# Launch_Tower_Ignition_Board_v6-3.net
KiCad netlist of a schematic drawn in EAGLE
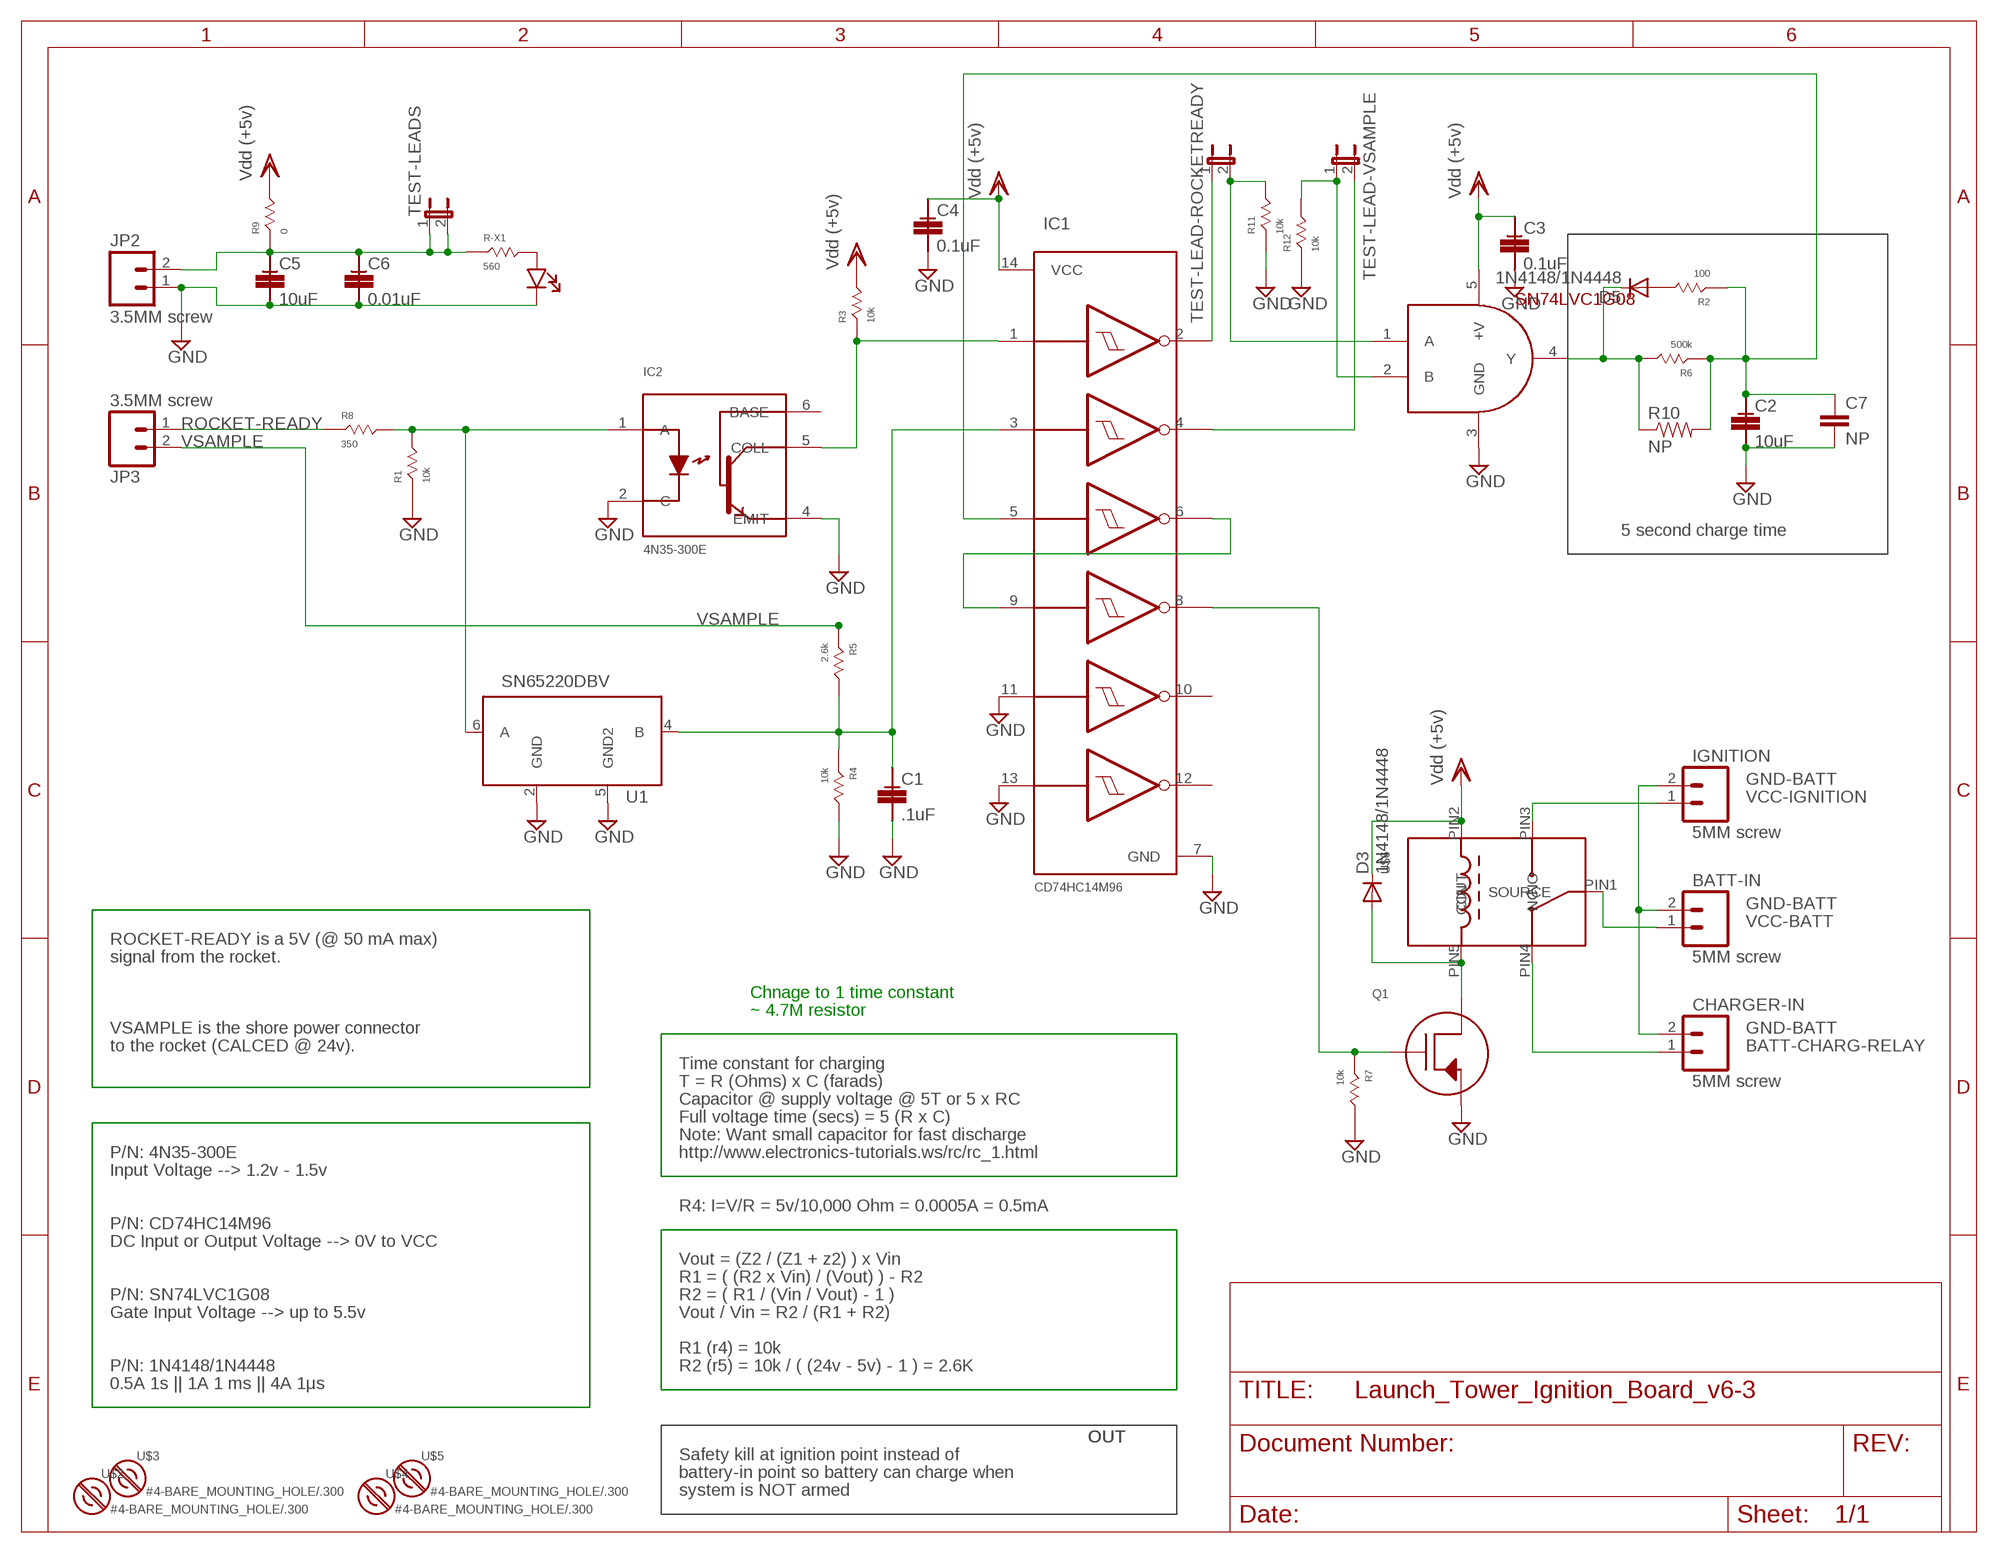
[diagram p0: schematic, sheet 1]

(export (version "E")
  (design (tool "Eeschema 10.0.6"))
  (components
    (comp (ref "BATT-IN")
      (value "5MM screw")
      (footprint "eagle-import:SCREWTERMINAL-5MM-2")
      (libsource (lib "eagle-import") (part "M025MM"))
    )
    (comp (ref "C1")
      (value ".1uF")
      (footprint "eagle-import:0805")
      (libsource (lib "eagle-import") (part "CAPACITOR-0805"))
    )
    (comp (ref "C2")
      (value "10uF")
      (footprint "eagle-import:0805")
      (libsource (lib "eagle-import") (part "CAPACITOR-0805"))
    )
    (comp (ref "C3")
      (value "0.1uF")
      (footprint "eagle-import:0805")
      (libsource (lib "eagle-import") (part "CAPACITOR-0805"))
    )
    (comp (ref "C4")
      (value "0.1uF")
      (footprint "eagle-import:0805")
      (libsource (lib "eagle-import") (part "CAPACITOR-0805"))
    )
    (comp (ref "C5")
      (value "10uF")
      (footprint "eagle-import:0805")
      (libsource (lib "eagle-import") (part "CAPACITOR-0805"))
    )
    (comp (ref "C6")
      (value "0.01uF")
      (footprint "eagle-import:0805")
      (libsource (lib "eagle-import") (part "CAPACITOR-0805"))
    )
    (comp (ref "C7")
      (value "NP")
      (footprint "eagle-import:CAP-PTH-SMALL")
      (libsource (lib "eagle-import") (part "CAPPTH"))
    )
    (comp (ref "CHARGER-IN")
      (value "5MM screw")
      (footprint "eagle-import:SCREWTERMINAL-5MM-2")
      (libsource (lib "eagle-import") (part "M025MM"))
    )
    (comp (ref "D3")
      (value "1N4148/1N4448")
      (footprint "eagle-import:DIODE-1N4001")
      (libsource (lib "eagle-import") (part "DIODEPTH"))
    )
    (comp (ref "D5")
      (value "1N4148/1N4448")
      (footprint "eagle-import:DIODE-1N4001")
      (libsource (lib "eagle-import") (part "DIODEPTH"))
    )
    (comp (ref "IC1")
      (value "INVERT GATES")
      (footprint "eagle-import:INVERTSOIC14")
      (libsource (lib "eagle-import") (part "HEX_INV_SHMITT_TRIG"))
    )
    (comp (ref "IC2")
      (value "OPTOISOLATOR")
      (footprint "eagle-import:4N35-300E")
      (libsource (lib "eagle-import") (part "OPTOISOLATOR"))
    )
    (comp (ref "IGNITION")
      (value "5MM screw")
      (footprint "eagle-import:SCREWTERMINAL-5MM-2")
      (libsource (lib "eagle-import") (part "M025MM"))
    )
    (comp (ref "JP2")
      (value "3.5MM screw")
      (footprint "eagle-import:SCREWTERMINAL-3.5MM-2")
      (libsource (lib "eagle-import") (part "M023.5MM"))
    )
    (comp (ref "JP3")
      (value "3.5MM screw")
      (footprint "eagle-import:SCREWTERMINAL-3.5MM-2")
      (libsource (lib "eagle-import") (part "M023.5MM"))
    )
    (comp (ref "LED-POWER-INDICATOR")
      (value "LED-550-XX04")
      (footprint "eagle-import:LED-550")
      (libsource (lib "eagle-import") (part "LED-550-XX04"))
    )
    (comp (ref "Q1")
      (value "NMOSFET")
      (footprint "eagle-import:FETSO-8")
      (libsource (lib "eagle-import") (part "NMOSFET"))
    )
    (comp (ref "R-X1")
      (value "560")
      (footprint "eagle-import:0805")
      (libsource (lib "eagle-import") (part "RESISTOR-0805"))
    )
    (comp (ref "R1")
      (value "10k")
      (footprint "eagle-import:0805")
      (libsource (lib "eagle-import") (part "RESISTOR-0805"))
    )
    (comp (ref "R2")
      (value "100")
      (footprint "eagle-import:0805")
      (libsource (lib "eagle-import") (part "RESISTOR-0805"))
    )
    (comp (ref "R3")
      (value "10k")
      (footprint "eagle-import:0805")
      (libsource (lib "eagle-import") (part "RESISTOR-0805"))
    )
    (comp (ref "R4")
      (value "10k")
      (footprint "eagle-import:0805")
      (libsource (lib "eagle-import") (part "RESISTOR-0805"))
    )
    (comp (ref "R5")
      (value "2.6k")
      (footprint "eagle-import:0805")
      (libsource (lib "eagle-import") (part "RESISTOR-0805"))
    )
    (comp (ref "R6")
      (value "500k")
      (footprint "eagle-import:0805")
      (libsource (lib "eagle-import") (part "RESISTOR-0805"))
    )
    (comp (ref "R7")
      (value "10k")
      (footprint "eagle-import:0805")
      (libsource (lib "eagle-import") (part "RESISTOR-0805"))
    )
    (comp (ref "R8")
      (value "350")
      (footprint "eagle-import:0805")
      (libsource (lib "eagle-import") (part "RESISTOR-0805"))
    )
    (comp (ref "R9")
      (value "0")
      (footprint "eagle-import:0805")
      (libsource (lib "eagle-import") (part "RESISTOR-0805"))
    )
    (comp (ref "R10")
      (value "NP")
      (footprint "eagle-import:AXIAL-0.4")
      (libsource (lib "eagle-import") (part "RESISTORPTH-1/4W"))
    )
    (comp (ref "R11")
      (value "10k")
      (footprint "eagle-import:0805")
      (libsource (lib "eagle-import") (part "RESISTOR-0805"))
    )
    (comp (ref "R12")
      (value "10k")
      (footprint "eagle-import:0805")
      (libsource (lib "eagle-import") (part "RESISTOR-0805"))
    )
    (comp (ref "TEST-LEAD-ROCKETREADY")
      (value "JUMPER-2PTH")
      (footprint "eagle-import:1X02")
      (libsource (lib "eagle-import") (part "JUMPER-2PTH"))
    )
    (comp (ref "TEST-LEAD-VSAMPLE")
      (value "JUMPER-2PTH")
      (footprint "eagle-import:1X02")
      (libsource (lib "eagle-import") (part "JUMPER-2PTH"))
    )
    (comp (ref "TEST-LEADS")
      (value "JUMPER-2PTH")
      (footprint "eagle-import:1X02")
      (libsource (lib "eagle-import") (part "JUMPER-2PTH"))
    )
    (comp (ref "U$1")
      (value "AND GATE")
      (footprint "eagle-import:SOT23-5")
      (libsource (lib "eagle-import") (part "SN74LVC1G08"))
    )
    (comp (ref "U$2")
      (value "#4-BARE_MOUNTING_HOLE/.300")
      (footprint "eagle-import:#4_.300-BARE+STD_NUT_OR_STAR_WASHER")
      (libsource (lib "eagle-import") (part "#4-BARE_MOUNTING_HOLE/.300"))
    )
    (comp (ref "U$3")
      (value "#4-BARE_MOUNTING_HOLE/.300")
      (footprint "eagle-import:#4_.300-BARE+STD_NUT_OR_STAR_WASHER")
      (libsource (lib "eagle-import") (part "#4-BARE_MOUNTING_HOLE/.300"))
    )
    (comp (ref "U$4")
      (value "#4-BARE_MOUNTING_HOLE/.300")
      (footprint "eagle-import:#4_.300-BARE+STD_NUT_OR_STAR_WASHER")
      (libsource (lib "eagle-import") (part "#4-BARE_MOUNTING_HOLE/.300"))
    )
    (comp (ref "U$5")
      (value "#4-BARE_MOUNTING_HOLE/.300")
      (footprint "eagle-import:#4_.300-BARE+STD_NUT_OR_STAR_WASHER")
      (libsource (lib "eagle-import") (part "#4-BARE_MOUNTING_HOLE/.300"))
    )
    (comp (ref "U$6")
      (value "RELAY-2")
      (footprint "eagle-import:G5LA")
      (libsource (lib "eagle-import") (part "RELAY-2"))
    )
    (comp (ref "U1")
      (value "SN65220DBV")
      (footprint "eagle-import:SOT23-6L")
      (libsource (lib "eagle-import") (part "SN65220DBV"))
    )
  )
  (nets
    (net (code "1") (name "/BATT-CHARG-RELAY") (class "Default")
      (node (ref "CHARGER-IN") (pin "1") (pinfunction "1_1") (pintype "passive"))
      (node (ref "U$6") (pin "PIN4") (pinfunction "NC_PIN4") (pintype "bidirectional"))
    )
    (net (code "2") (name "/GND-BATT") (class "Default")
      (node (ref "BATT-IN") (pin "2") (pinfunction "2_2") (pintype "passive"))
      (node (ref "CHARGER-IN") (pin "2") (pinfunction "2_2") (pintype "passive"))
      (node (ref "IGNITION") (pin "2") (pinfunction "2_2") (pintype "passive"))
    )
    (net (code "3") (name "/ROCKET-READY") (class "Default")
      (node (ref "IC2") (pin "1") (pinfunction "A_1") (pintype "bidirectional"))
      (node (ref "R1") (pin "CATHODE") (pinfunction "CATHODE_CATHODE") (pintype "bidirectional"))
      (node (ref "R8") (pin "CATHODE") (pinfunction "CATHODE_CATHODE") (pintype "bidirectional"))
      (node (ref "U1") (pin "6") (pinfunction "A_6") (pintype "passive"))
    )
    (net (code "4") (name "/VCC-BATT") (class "Default")
      (node (ref "BATT-IN") (pin "1") (pinfunction "1_1") (pintype "passive"))
      (node (ref "U$6") (pin "PIN1") (pinfunction "SOURCE_PIN1") (pintype "bidirectional"))
    )
    (net (code "5") (name "/VCC-IGNITION") (class "Default")
      (node (ref "IGNITION") (pin "1") (pinfunction "1_1") (pintype "passive"))
      (node (ref "U$6") (pin "PIN3") (pinfunction "NO_PIN3") (pintype "bidirectional"))
    )
    (net (code "6") (name "/VSAMPLE") (class "Default")
      (node (ref "JP3") (pin "2") (pinfunction "2_2") (pintype "passive"))
      (node (ref "R5") (pin "ANODE") (pinfunction "ANODE_ANODE") (pintype "bidirectional"))
    )
    (net (code "7") (name "GND") (class "Default")
      (node (ref "C1") (pin "CATHODE") (pinfunction "CATHODE_CATHODE") (pintype "bidirectional"))
      (node (ref "C2") (pin "CATHODE") (pinfunction "CATHODE_CATHODE") (pintype "bidirectional"))
      (node (ref "C3") (pin "CATHODE") (pinfunction "CATHODE_CATHODE") (pintype "bidirectional"))
      (node (ref "C4") (pin "CATHODE") (pinfunction "CATHODE_CATHODE") (pintype "bidirectional"))
      (node (ref "C5") (pin "CATHODE") (pinfunction "CATHODE_CATHODE") (pintype "bidirectional"))
      (node (ref "C6") (pin "CATHODE") (pinfunction "CATHODE_CATHODE") (pintype "bidirectional"))
      (node (ref "C7") (pin "2") (pinfunction "2_2") (pintype "passive"))
      (node (ref "IC1") (pin "11") (pinfunction "5A_11") (pintype "input"))
      (node (ref "IC1") (pin "13") (pinfunction "6A_13") (pintype "input"))
      (node (ref "IC1") (pin "7") (pinfunction "GND_7") (pintype "bidirectional"))
      (node (ref "IC2") (pin "2") (pinfunction "C_2") (pintype "bidirectional"))
      (node (ref "IC2") (pin "4") (pinfunction "EMIT_4") (pintype "bidirectional"))
      (node (ref "JP2") (pin "1") (pinfunction "1_1") (pintype "passive"))
      (node (ref "LED-POWER-INDICATOR") (pin "CATHODE") (pinfunction "CATHODE_CATHODE") (pintype "bidirectional"))
      (node (ref "Q1") (pin "1") (pinfunction "SOURCE_1") (pintype "bidirectional"))
      (node (ref "R1") (pin "ANODE") (pinfunction "ANODE_ANODE") (pintype "bidirectional"))
      (node (ref "R11") (pin "ANODE") (pinfunction "ANODE_ANODE") (pintype "bidirectional"))
      (node (ref "R12") (pin "ANODE") (pinfunction "ANODE_ANODE") (pintype "bidirectional"))
      (node (ref "R4") (pin "CATHODE") (pinfunction "CATHODE_CATHODE") (pintype "bidirectional"))
      (node (ref "R7") (pin "CATHODE") (pinfunction "CATHODE_CATHODE") (pintype "bidirectional"))
      (node (ref "U$1") (pin "3") (pinfunction "GND_3") (pintype "bidirectional"))
      (node (ref "U1") (pin "2") (pinfunction "GND_2") (pintype "power_in"))
      (node (ref "U1") (pin "5") (pinfunction "GND2_5") (pintype "power_in"))
    )
    (net (code "8") (name "Net-(C5-PadANODE)") (class "Default")
      (node (ref "C5") (pin "ANODE") (pinfunction "ANODE_ANODE") (pintype "bidirectional"))
      (node (ref "C6") (pin "ANODE") (pinfunction "ANODE_ANODE") (pintype "bidirectional"))
      (node (ref "JP2") (pin "2") (pinfunction "2_2") (pintype "passive"))
      (node (ref "R-X1") (pin "ANODE") (pinfunction "ANODE_ANODE") (pintype "bidirectional"))
      (node (ref "R9") (pin "ANODE") (pinfunction "ANODE_ANODE") (pintype "bidirectional"))
      (node (ref "TEST-LEADS") (pin "1") (pinfunction "1_1") (pintype "passive"))
      (node (ref "TEST-LEADS") (pin "2") (pinfunction "2_2") (pintype "passive"))
    )
    (net (code "9") (name "Net-(D5-PadA)") (class "Default")
      (node (ref "D5") (pin "A") (pinfunction "A_A") (pintype "passive"))
      (node (ref "R2") (pin "CATHODE") (pinfunction "CATHODE_CATHODE") (pintype "bidirectional"))
    )
    (net (code "10") (name "Net-(IC1-1A)") (class "Default")
      (node (ref "IC1") (pin "1") (pinfunction "1A_1") (pintype "input"))
      (node (ref "IC2") (pin "5") (pinfunction "COLL_5") (pintype "bidirectional"))
      (node (ref "R3") (pin "ANODE") (pinfunction "ANODE_ANODE") (pintype "bidirectional"))
    )
    (net (code "11") (name "Net-(IC1-1Y)") (class "Default")
      (node (ref "IC1") (pin "2") (pinfunction "1Y_2") (pintype "output"))
      (node (ref "TEST-LEAD-ROCKETREADY") (pin "1") (pinfunction "1_1") (pintype "passive"))
    )
    (net (code "12") (name "Net-(IC1-2A)") (class "Default")
      (node (ref "C1") (pin "ANODE") (pinfunction "ANODE_ANODE") (pintype "bidirectional"))
      (node (ref "IC1") (pin "3") (pinfunction "2A_3") (pintype "input"))
      (node (ref "R4") (pin "ANODE") (pinfunction "ANODE_ANODE") (pintype "bidirectional"))
      (node (ref "R5") (pin "CATHODE") (pinfunction "CATHODE_CATHODE") (pintype "bidirectional"))
      (node (ref "U1") (pin "4") (pinfunction "B_4") (pintype "passive"))
    )
    (net (code "13") (name "Net-(IC1-2Y)") (class "Default")
      (node (ref "IC1") (pin "4") (pinfunction "2Y_4") (pintype "output"))
      (node (ref "TEST-LEAD-VSAMPLE") (pin "2") (pinfunction "2_2") (pintype "passive"))
    )
    (net (code "14") (name "Net-(IC1-3A)") (class "Default")
      (node (ref "C2") (pin "ANODE") (pinfunction "ANODE_ANODE") (pintype "bidirectional"))
      (node (ref "C7") (pin "1") (pinfunction "1_1") (pintype "passive"))
      (node (ref "IC1") (pin "5") (pinfunction "3A_5") (pintype "input"))
      (node (ref "R10") (pin "P$2") (pinfunction "2_P$2") (pintype "passive"))
      (node (ref "R2") (pin "ANODE") (pinfunction "ANODE_ANODE") (pintype "bidirectional"))
      (node (ref "R6") (pin "ANODE") (pinfunction "ANODE_ANODE") (pintype "bidirectional"))
    )
    (net (code "15") (name "Net-(IC1-3Y)") (class "Default")
      (node (ref "IC1") (pin "6") (pinfunction "3Y_6") (pintype "output"))
      (node (ref "IC1") (pin "9") (pinfunction "4A_9") (pintype "input"))
    )
    (net (code "16") (name "Net-(IC1-4Y)") (class "Default")
      (node (ref "IC1") (pin "8") (pinfunction "4Y_8") (pintype "output"))
      (node (ref "Q1") (pin "4") (pinfunction "GATE_4") (pintype "bidirectional"))
      (node (ref "R7") (pin "ANODE") (pinfunction "ANODE_ANODE") (pintype "bidirectional"))
    )
    (net (code "17") (name "Net-(JP3-Pad1)") (class "Default")
      (node (ref "JP3") (pin "1") (pinfunction "1_1") (pintype "passive"))
      (node (ref "R8") (pin "ANODE") (pinfunction "ANODE_ANODE") (pintype "bidirectional"))
    )
    (net (code "18") (name "Net-(LED-POWER-INDICATOR-PadANODE)") (class "Default")
      (node (ref "LED-POWER-INDICATOR") (pin "ANODE") (pinfunction "ANODE_ANODE") (pintype "bidirectional"))
      (node (ref "R-X1") (pin "CATHODE") (pinfunction "CATHODE_CATHODE") (pintype "bidirectional"))
    )
    (net (code "19") (name "Net-(Q1-DRAIN)") (class "Default")
      (node (ref "D3") (pin "A") (pinfunction "A_A") (pintype "passive"))
      (node (ref "Q1") (pin "5") (pinfunction "DRAIN_5") (pintype "bidirectional"))
      (node (ref "U$6") (pin "PIN5") (pinfunction "CIN_PIN5") (pintype "bidirectional"))
    )
    (net (code "20") (name "Net-(R10-1)") (class "Default")
      (node (ref "D5") (pin "C") (pinfunction "C_C") (pintype "passive"))
      (node (ref "R10") (pin "P$1") (pinfunction "1_P$1") (pintype "passive"))
      (node (ref "R6") (pin "CATHODE") (pinfunction "CATHODE_CATHODE") (pintype "bidirectional"))
      (node (ref "U$1") (pin "4") (pinfunction "Y_4") (pintype "bidirectional"))
    )
    (net (code "21") (name "Net-(U$1-A)") (class "Default")
      (node (ref "R11") (pin "CATHODE") (pinfunction "CATHODE_CATHODE") (pintype "bidirectional"))
      (node (ref "TEST-LEAD-ROCKETREADY") (pin "2") (pinfunction "2_2") (pintype "passive"))
      (node (ref "U$1") (pin "1") (pinfunction "A_1") (pintype "bidirectional"))
    )
    (net (code "22") (name "Net-(U$1-B)") (class "Default")
      (node (ref "R12") (pin "CATHODE") (pinfunction "CATHODE_CATHODE") (pintype "bidirectional"))
      (node (ref "TEST-LEAD-VSAMPLE") (pin "1") (pinfunction "1_1") (pintype "passive"))
      (node (ref "U$1") (pin "2") (pinfunction "B_2") (pintype "bidirectional"))
    )
    (net (code "23") (name "Vdd (+5v)") (class "Default")
      (node (ref "C3") (pin "ANODE") (pinfunction "ANODE_ANODE") (pintype "bidirectional"))
      (node (ref "C4") (pin "ANODE") (pinfunction "ANODE_ANODE") (pintype "bidirectional"))
      (node (ref "D3") (pin "C") (pinfunction "C_C") (pintype "passive"))
      (node (ref "IC1") (pin "14") (pinfunction "VCC_14") (pintype "bidirectional"))
      (node (ref "R3") (pin "CATHODE") (pinfunction "CATHODE_CATHODE") (pintype "bidirectional"))
      (node (ref "R9") (pin "CATHODE") (pinfunction "CATHODE_CATHODE") (pintype "bidirectional"))
      (node (ref "U$1") (pin "5") (pinfunction "+V_5") (pintype "bidirectional"))
      (node (ref "U$6") (pin "PIN2") (pinfunction "COUT_PIN2") (pintype "bidirectional"))
    )
    (net (code "24") (name "unconnected-(IC1-5Y-Pad10)") (class "Default")
      (node (ref "IC1") (pin "10") (pinfunction "5Y_10") (pintype "output"))
    )
    (net (code "25") (name "unconnected-(IC1-6Y-Pad12)") (class "Default")
      (node (ref "IC1") (pin "12") (pinfunction "6Y_12") (pintype "output"))
    )
    (net (code "26") (name "unconnected-(IC2-BASE-Pad6)") (class "Default")
      (node (ref "IC2") (pin "6") (pinfunction "BASE_6") (pintype "bidirectional"))
    )
  )
)
